# esp32-hub75-driver-schem.net
KiCad netlist of a schematic drawn in EasyEDA
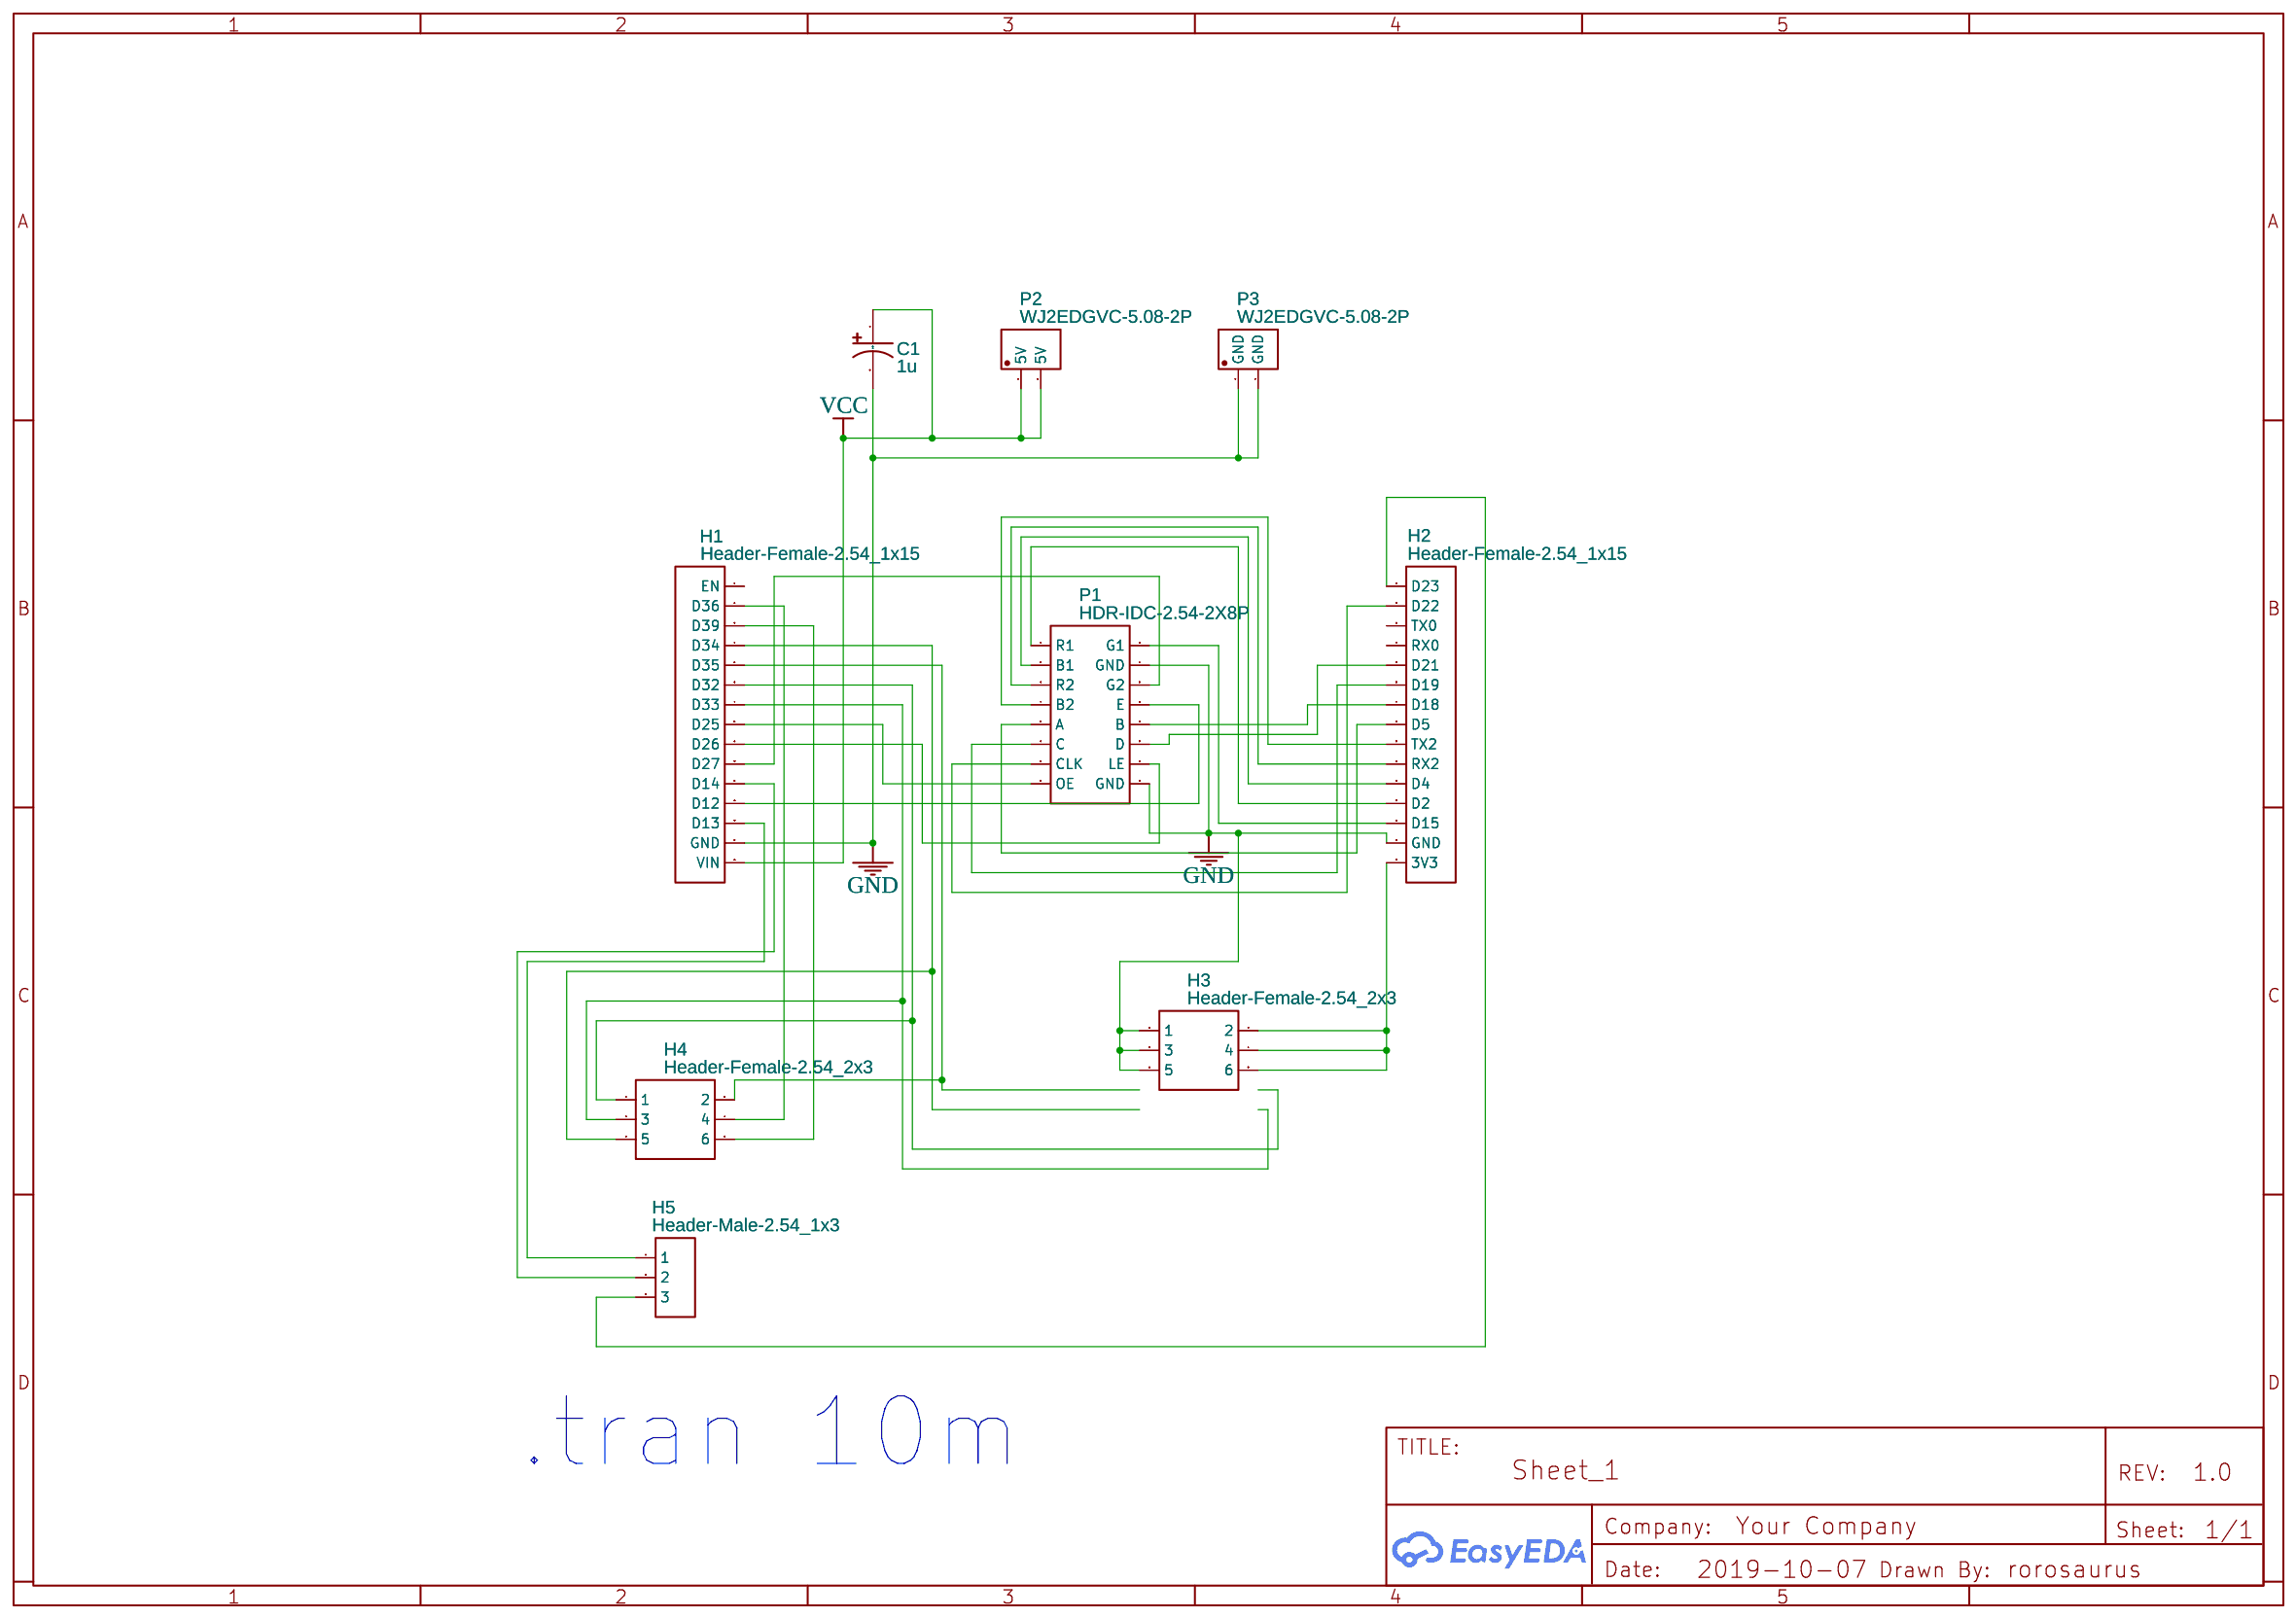
[diagram p0: schematic sheet]

(export (version "E")
  (design (tool "Eeschema 10.0.6"))
  (components
    (comp (ref "C1") (value "1u") (libsource (lib "") (part "Cap_Electrolytic(TH)_D10.0XF5.0_US")))
    (comp (ref "H1")
      (value "Header-Female-2.54_1x15")
      (fields
        (field (name "BOM_Manufacturer Part") "220S-1*15P H=8.5MM Ytype Gold-plated")
        (field (name "BOM_Supplier Part") "C124408")
      )
      (libsource (lib "") (part "Unknown_350_365"))
    )
    (comp (ref "H2")
      (value "Header-Female-2.54_1x15")
      (fields
        (field (name "BOM_Manufacturer Part") "220S-1*15P H=8.5MM Ytype Gold-plated")
        (field (name "BOM_Supplier Part") "C124408")
      )
      (libsource (lib "") (part "Unknown_715_365"))
    )
    (comp (ref "H3")
      (value "Header-Female-2.54_2x3")
      (fields
        (field (name "BOM_Manufacturer Part") "DS1023-2*3SF11")
        (field (name "BOM_Supplier Part") "C92272")
      )
      (libsource (lib "") (part "Unknown_600_525"))
    )
    (comp (ref "H4")
      (value "Header-Female-2.54_2x3")
      (fields
        (field (name "BOM_Manufacturer Part") "DS1023-2*3SF11")
        (field (name "BOM_Supplier Part") "C92272")
      )
      (libsource (lib "") (part "Unknown_335_560"))
    )
    (comp (ref "H5")
      (value "Header-Male-2.54_1x3")
      (fields
        (field (name "BOM_Manufacturer Part") "Header2.54mm 1*3P")
        (field (name "BOM_Supplier Part") "C49257")
      )
      (libsource (lib "") (part "Unknown_330_640"))
    )
    (comp (ref "P1")
      (value "HDR-IDC-2.54-2X8P")
      (fields
        (field (name "BOM_Manufacturer Part") "IDC Box 2.54mm 16P　Straight")
        (field (name "BOM_Supplier Part") "C3406")
      )
      (libsource (lib "") (part "Unknown_545_355"))
    )
    (comp (ref "P2")
      (value "WJ2EDGVC-5.08-2P")
      (fields (field (name "BOM_Supplier Part") "C8445"))
      (libsource (lib "") (part "Unknown_515_175"))
    )
    (comp (ref "P3")
      (value "WJ2EDGVC-5.08-2P")
      (fields (field (name "BOM_Supplier Part") "C8445"))
      (libsource (lib "") (part "Unknown_625_175"))
    )
  )
  (nets
    (net (code "1") (name "GND") (class "Default")
      (node (ref "C1") (pin "2") (pinfunction "2_2") (pintype "unspecified"))
      (node (ref "H1") (pin "14") (pinfunction "GND_14") (pintype "unspecified"))
      (node (ref "H2") (pin "14") (pinfunction "GND_14") (pintype "unspecified"))
      (node (ref "H3") (pin "1") (pinfunction "1_1") (pintype "input"))
      (node (ref "H3") (pin "3") (pinfunction "3_3") (pintype "input"))
      (node (ref "H3") (pin "5") (pinfunction "5_5") (pintype "input"))
      (node (ref "P1") (pin "16") (pinfunction "GND_16") (pintype "unspecified"))
      (node (ref "P1") (pin "4") (pinfunction "GND_4") (pintype "unspecified"))
      (node (ref "P3") (pin "1") (pinfunction "GND_1") (pintype "unspecified"))
      (node (ref "P3") (pin "2") (pinfunction "GND_2") (pintype "unspecified"))
    )
    (net (code "2") (name "Net-(H1-D12)") (class "Default")
      (node (ref "H1") (pin "12") (pinfunction "D12_12") (pintype "unspecified"))
      (node (ref "P1") (pin "8") (pinfunction "E_8") (pintype "unspecified"))
    )
    (net (code "3") (name "Net-(H1-D13)") (class "Default")
      (node (ref "H1") (pin "13") (pinfunction "D13_13") (pintype "unspecified"))
      (node (ref "H5") (pin "1") (pinfunction "1_1") (pintype "input"))
    )
    (net (code "4") (name "Net-(H1-D14)") (class "Default")
      (node (ref "H1") (pin "11") (pinfunction "D14_11") (pintype "unspecified"))
      (node (ref "H5") (pin "2") (pinfunction "2_2") (pintype "input"))
    )
    (net (code "5") (name "Net-(H1-D25)") (class "Default")
      (node (ref "H1") (pin "8") (pinfunction "D25_8") (pintype "unspecified"))
      (node (ref "P1") (pin "15") (pinfunction "OE_15") (pintype "unspecified"))
    )
    (net (code "6") (name "Net-(H1-D26)") (class "Default")
      (node (ref "H1") (pin "9") (pinfunction "D26_9") (pintype "unspecified"))
      (node (ref "P1") (pin "14") (pinfunction "LE_14") (pintype "unspecified"))
    )
    (net (code "7") (name "Net-(H1-D27)") (class "Default")
      (node (ref "H1") (pin "10") (pinfunction "D27_10") (pintype "unspecified"))
      (node (ref "P1") (pin "6") (pinfunction "G2_6") (pintype "unspecified"))
    )
    (net (code "8") (name "Net-(H1-D32)") (class "Default")
      (node (ref "H1") (pin "6") (pinfunction "D32_6") (pintype "unspecified"))
      (node (ref "H4") (pin "1") (pinfunction "1_1") (pintype "input"))
    )
    (net (code "9") (name "Net-(H1-D33)") (class "Default")
      (node (ref "H1") (pin "7") (pinfunction "D33_7") (pintype "unspecified"))
      (node (ref "H4") (pin "3") (pinfunction "3_3") (pintype "input"))
    )
    (net (code "10") (name "Net-(H1-D34)") (class "Default")
      (node (ref "H1") (pin "4") (pinfunction "D34_4") (pintype "unspecified"))
      (node (ref "H4") (pin "5") (pinfunction "5_5") (pintype "input"))
    )
    (net (code "11") (name "Net-(H1-D35)") (class "Default")
      (node (ref "H1") (pin "5") (pinfunction "D35_5") (pintype "unspecified"))
      (node (ref "H4") (pin "2") (pinfunction "2_2") (pintype "input"))
    )
    (net (code "12") (name "Net-(H1-D36)") (class "Default")
      (node (ref "H1") (pin "2") (pinfunction "D36_2") (pintype "unspecified"))
      (node (ref "H4") (pin "4") (pinfunction "4_4") (pintype "input"))
    )
    (net (code "13") (name "Net-(H1-D39)") (class "Default")
      (node (ref "H1") (pin "3") (pinfunction "D39_3") (pintype "unspecified"))
      (node (ref "H4") (pin "6") (pinfunction "6_6") (pintype "input"))
    )
    (net (code "14") (name "Net-(H2-3V3)") (class "Default")
      (node (ref "H2") (pin "15") (pinfunction "3V3_15") (pintype "unspecified"))
      (node (ref "H3") (pin "2") (pinfunction "2_2") (pintype "input"))
      (node (ref "H3") (pin "4") (pinfunction "4_4") (pintype "input"))
      (node (ref "H3") (pin "6") (pinfunction "6_6") (pintype "input"))
    )
    (net (code "15") (name "Net-(H2-D2)") (class "Default")
      (node (ref "H2") (pin "12") (pinfunction "D2_12") (pintype "unspecified"))
      (node (ref "P1") (pin "1") (pinfunction "R1_1") (pintype "unspecified"))
    )
    (net (code "16") (name "Net-(H2-D4)") (class "Default")
      (node (ref "H2") (pin "11") (pinfunction "D4_11") (pintype "unspecified"))
      (node (ref "P1") (pin "3") (pinfunction "B1_3") (pintype "unspecified"))
    )
    (net (code "17") (name "Net-(H2-D5)") (class "Default")
      (node (ref "H2") (pin "8") (pinfunction "D5_8") (pintype "unspecified"))
      (node (ref "P1") (pin "9") (pinfunction "A_9") (pintype "unspecified"))
    )
    (net (code "18") (name "Net-(H2-D15)") (class "Default")
      (node (ref "H2") (pin "13") (pinfunction "D15_13") (pintype "unspecified"))
      (node (ref "P1") (pin "2") (pinfunction "G1_2") (pintype "unspecified"))
    )
    (net (code "19") (name "Net-(H2-D18)") (class "Default")
      (node (ref "H2") (pin "7") (pinfunction "D18_7") (pintype "unspecified"))
      (node (ref "P1") (pin "10") (pinfunction "B_10") (pintype "unspecified"))
    )
    (net (code "20") (name "Net-(H2-D19)") (class "Default")
      (node (ref "H2") (pin "6") (pinfunction "D19_6") (pintype "unspecified"))
      (node (ref "P1") (pin "11") (pinfunction "C_11") (pintype "unspecified"))
    )
    (net (code "21") (name "Net-(H2-D21)") (class "Default")
      (node (ref "H2") (pin "5") (pinfunction "D21_5") (pintype "unspecified"))
      (node (ref "P1") (pin "12") (pinfunction "D_12") (pintype "unspecified"))
    )
    (net (code "22") (name "Net-(H2-D22)") (class "Default")
      (node (ref "H2") (pin "2") (pinfunction "D22_2") (pintype "unspecified"))
      (node (ref "P1") (pin "13") (pinfunction "CLK_13") (pintype "unspecified"))
    )
    (net (code "23") (name "Net-(H2-D23)") (class "Default")
      (node (ref "H2") (pin "1") (pinfunction "D23_1") (pintype "unspecified"))
      (node (ref "H5") (pin "3") (pinfunction "3_3") (pintype "input"))
    )
    (net (code "24") (name "Net-(H2-RX2)") (class "Default")
      (node (ref "H2") (pin "10") (pinfunction "RX2_10") (pintype "unspecified"))
      (node (ref "P1") (pin "5") (pinfunction "R2_5") (pintype "unspecified"))
    )
    (net (code "25") (name "Net-(H2-TX2)") (class "Default")
      (node (ref "H2") (pin "9") (pinfunction "TX2_9") (pintype "unspecified"))
      (node (ref "P1") (pin "7") (pinfunction "B2_7") (pintype "unspecified"))
    )
    (net (code "26") (name "VCC") (class "Default")
      (node (ref "C1") (pin "1") (pinfunction "1_1") (pintype "unspecified"))
      (node (ref "H1") (pin "15") (pinfunction "VIN_15") (pintype "unspecified"))
      (node (ref "P2") (pin "1") (pinfunction "5V_1") (pintype "unspecified"))
      (node (ref "P2") (pin "2") (pinfunction "5V_2") (pintype "unspecified"))
    )
    (net (code "27") (name "unconnected-(H1-EN-Pad1)") (class "Default")
      (node (ref "H1") (pin "1") (pinfunction "EN_1") (pintype "unspecified"))
    )
    (net (code "28") (name "unconnected-(H2-RX0-Pad4)") (class "Default")
      (node (ref "H2") (pin "4") (pinfunction "RX0_4") (pintype "unspecified"))
    )
    (net (code "29") (name "unconnected-(H2-TX0-Pad3)") (class "Default")
      (node (ref "H2") (pin "3") (pinfunction "TX0_3") (pintype "unspecified"))
    )
  )
)
